# design.net
KiCad netlist of a schematic drawn in Altium Designer
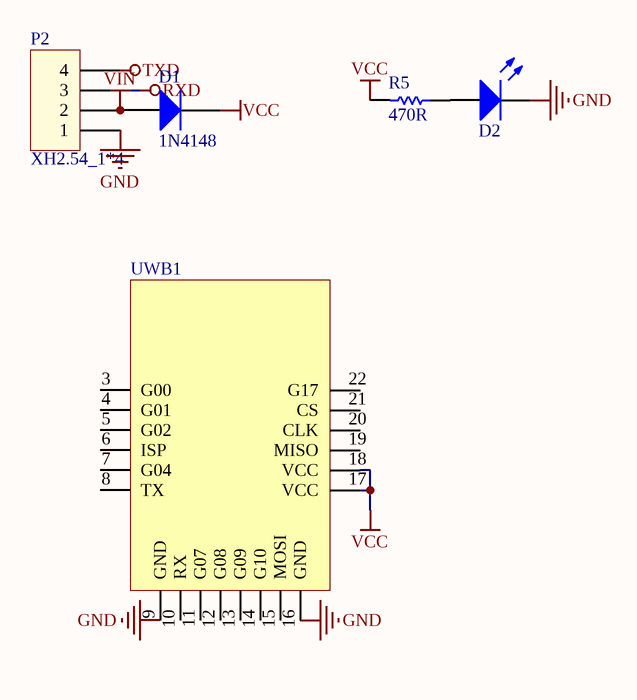
[diagram p0: 信标底板原理图.SchDoc]

(export (version "E")
  (design (tool "Eeschema 10.0.6"))
  (components
    (comp (ref "D1") (value "1N4148") (footprint "SM0805Z_S") (libsource (lib "MIAO") (part "1N4148")))
    (comp (ref "D2") (value "LED") (footprint "LED[0603]") (libsource (lib "MIAO") (part "LED")))
    (comp (ref "P2")
      (value "XH2.54_1*4")
      (footprint "XH2.54-LI-4P")
      (libsource (lib "MIAO") (part "XH2.54_1*4"))
    )
    (comp (ref "R5") (value "470R") (footprint "ALX_0603A") (libsource (lib "MIAO") (part "ALX_RES")))
    (comp (ref "UWB1") (value "~") (libsource (lib "MIAO") (part "MK1000")))
  )
  (nets
    (net (code "1") (name "GND") (class "Default")
      (node (ref "D2") (pin "2") (pinfunction "K_2") (pintype "passive"))
      (node (ref "P2") (pin "1") (pinfunction "1_1") (pintype "passive"))
      (node (ref "UWB1") (pin "16") (pinfunction "GND_16") (pintype "passive"))
      (node (ref "UWB1") (pin "9") (pinfunction "GND_9") (pintype "passive"))
    )
    (net (code "2") (name "Net-(D2-A)") (class "Default")
      (node (ref "D2") (pin "1") (pinfunction "A_1") (pintype "passive"))
      (node (ref "R5") (pin "1") (pinfunction "1_1") (pintype "passive"))
    )
    (net (code "3") (name "RXD") (class "Default")
      (node (ref "P2") (pin "3") (pinfunction "3_3") (pintype "passive"))
    )
    (net (code "4") (name "TXD") (class "Default")
      (node (ref "P2") (pin "4") (pinfunction "4_4") (pintype "passive"))
    )
    (net (code "5") (name "VCC") (class "Default")
      (node (ref "D1") (pin "2") (pintype "passive"))
      (node (ref "R5") (pin "2") (pinfunction "2_2") (pintype "passive"))
      (node (ref "UWB1") (pin "17") (pinfunction "VCC_17") (pintype "passive"))
      (node (ref "UWB1") (pin "18") (pinfunction "VCC_18") (pintype "passive"))
    )
    (net (code "6") (name "VIN") (class "Default")
      (node (ref "D1") (pin "1") (pintype "passive"))
      (node (ref "P2") (pin "2") (pinfunction "2_2") (pintype "passive"))
    )
    (net (code "7") (name "unconnected-(UWB1-CLK-Pad20)") (class "Default")
      (node (ref "UWB1") (pin "20") (pinfunction "CLK_20") (pintype "passive"))
    )
    (net (code "8") (name "unconnected-(UWB1-CS-Pad21)") (class "Default")
      (node (ref "UWB1") (pin "21") (pinfunction "CS_21") (pintype "passive"))
    )
    (net (code "9") (name "unconnected-(UWB1-G00-Pad3)") (class "Default")
      (node (ref "UWB1") (pin "3") (pinfunction "G00_3") (pintype "passive"))
    )
    (net (code "10") (name "unconnected-(UWB1-G01-Pad4)") (class "Default")
      (node (ref "UWB1") (pin "4") (pinfunction "G01_4") (pintype "passive"))
    )
    (net (code "11") (name "unconnected-(UWB1-G02-Pad5)") (class "Default")
      (node (ref "UWB1") (pin "5") (pinfunction "G02_5") (pintype "passive"))
    )
    (net (code "12") (name "unconnected-(UWB1-G04-Pad7)") (class "Default")
      (node (ref "UWB1") (pin "7") (pinfunction "G04_7") (pintype "passive"))
    )
    (net (code "13") (name "unconnected-(UWB1-G07-Pad11)") (class "Default")
      (node (ref "UWB1") (pin "11") (pinfunction "G07_11") (pintype "passive"))
    )
    (net (code "14") (name "unconnected-(UWB1-G08-Pad12)") (class "Default")
      (node (ref "UWB1") (pin "12") (pinfunction "G08_12") (pintype "passive"))
    )
    (net (code "15") (name "unconnected-(UWB1-G09-Pad13)") (class "Default")
      (node (ref "UWB1") (pin "13") (pinfunction "G09_13") (pintype "passive"))
    )
    (net (code "16") (name "unconnected-(UWB1-G10-Pad14)") (class "Default")
      (node (ref "UWB1") (pin "14") (pinfunction "G10_14") (pintype "passive"))
    )
    (net (code "17") (name "unconnected-(UWB1-G17-Pad22)") (class "Default")
      (node (ref "UWB1") (pin "22") (pinfunction "G17_22") (pintype "passive"))
    )
    (net (code "18") (name "unconnected-(UWB1-ISP-Pad6)") (class "Default")
      (node (ref "UWB1") (pin "6") (pinfunction "ISP_6") (pintype "passive"))
    )
    (net (code "19") (name "unconnected-(UWB1-MISO-Pad19)") (class "Default")
      (node (ref "UWB1") (pin "19") (pinfunction "MISO_19") (pintype "passive"))
    )
    (net (code "20") (name "unconnected-(UWB1-MOSI-Pad15)") (class "Default")
      (node (ref "UWB1") (pin "15") (pinfunction "MOSI_15") (pintype "passive"))
    )
    (net (code "21") (name "unconnected-(UWB1-RX-Pad10)") (class "Default")
      (node (ref "UWB1") (pin "10") (pinfunction "RX_10") (pintype "passive"))
    )
    (net (code "22") (name "unconnected-(UWB1-TX-Pad8)") (class "Default")
      (node (ref "UWB1") (pin "8") (pinfunction "TX_8") (pintype "passive"))
    )
  )
)
